# CONTROL.net
KiCad netlist of a schematic drawn in Altium Designer
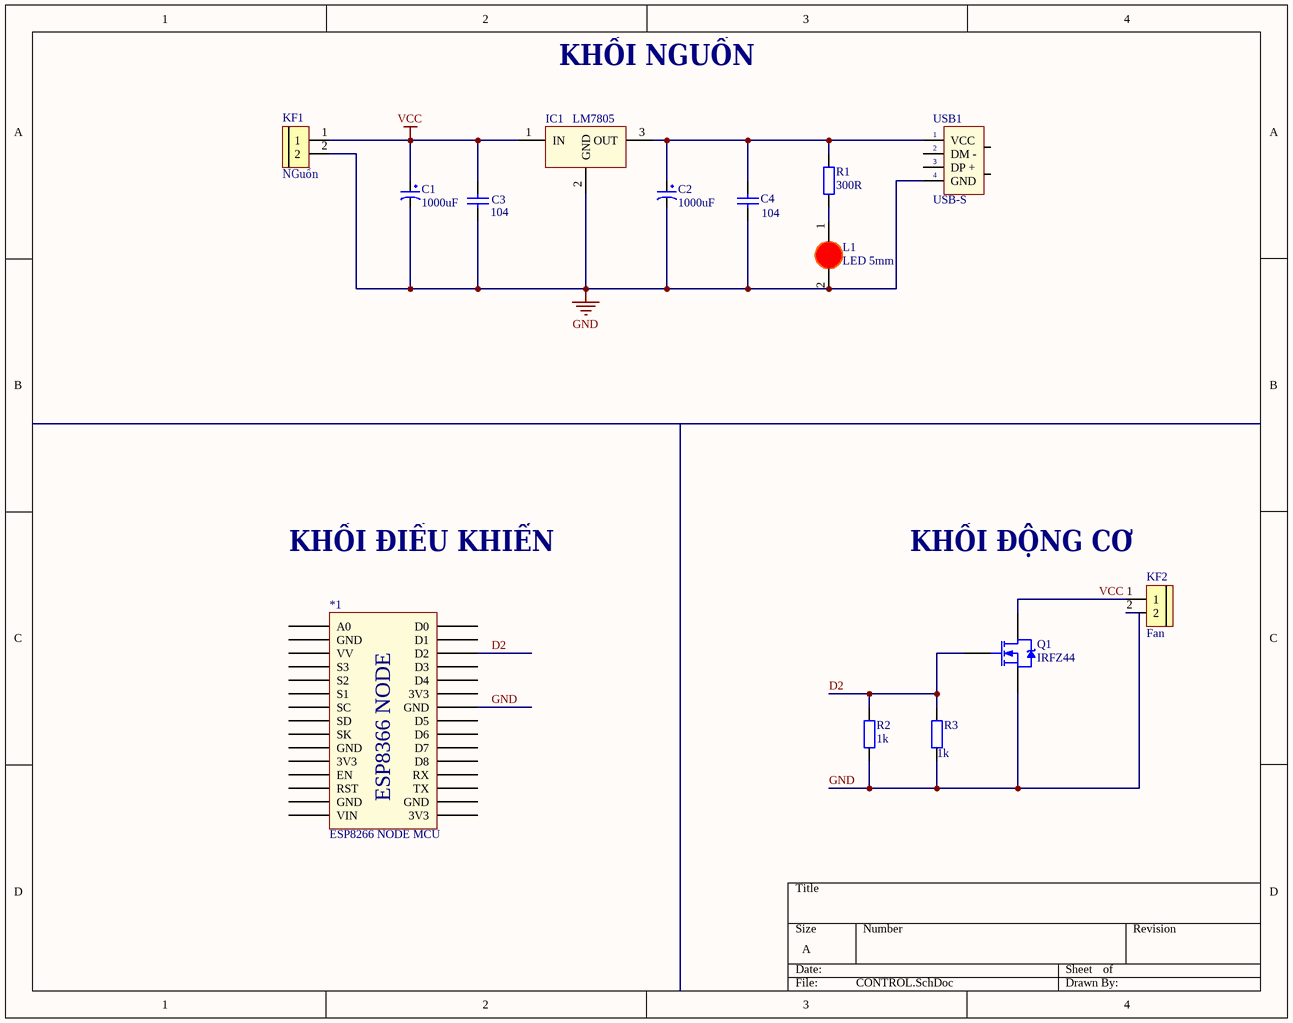
[diagram p0: CONTROL.SchDoc]

(export (version "E")
  (design (tool "Eeschema 10.0.6"))
  (components
    (comp (ref "*1")
      (value "ESP8266 NODE MCU")
      (footprint "ESP8266 NODE MCU")
      (libsource (lib "Module") (part "ESP8266 NODE MCU"))
    )
    (comp (ref "C1")
      (value "1000uF")
      (footprint "tu hoa 10mm")
      (description "Cắm")
      (libsource (lib "Capacitor") (part "Tu Hoa 1000uF 10V 10x12"))
    )
    (comp (ref "C2")
      (value "1000uF")
      (footprint "tu hoa 10mm")
      (description "Cắm")
      (libsource (lib "Capacitor") (part "Tu Hoa 1000uF 10V 10x12"))
    )
    (comp (ref "C3")
      (value "104")
      (footprint "tu gom")
      (description "Cắm")
      (libsource (lib "Capacitor") (part "Tu gom 104 50V"))
    )
    (comp (ref "C4")
      (value "104")
      (footprint "tu gom")
      (description "Cắm")
      (libsource (lib "Capacitor") (part "Tu gom 104 50V"))
    )
    (comp (ref "IC1")
      (value "LM7805")
      (footprint "QTO-220")
      (description "On ap +, from + 5 to + 24VDC")
      (libsource (lib "Cty1") (part "LM78xx"))
    )
    (comp (ref "KF1")
      (value "NGuồn")
      (footprint "Con 2 KF301 5.08")
      (description "Cắm")
      (libsource (lib "") (part "CON 2 KF301_1"))
    )
    (comp (ref "KF2")
      (value "Fan")
      (footprint "Con 2 KF301 5.08")
      (description "Cắm")
      (libsource (lib "Connector") (part "CON 2 KF301"))
    )
    (comp (ref "L1")
      (value "LED 5mm")
      (footprint "LED-5MM-RED")
      (description "Cắm")
      (libsource (lib "Led") (part "LED 5mm Do"))
    )
    (comp (ref "Q1")
      (value "IRFZ44")
      (footprint "TO220")
      (description "TO-220")
      (libsource (lib "TranFet") (part "FET IRFZ44 DIP"))
    )
    (comp (ref "R1")
      (value "300R")
      (footprint "tro vach 1/4w")
      (description "Cắm")
      (libsource (lib "Resistor") (part "Tro Vach 1/4W 5% 300R"))
    )
    (comp (ref "R2")
      (value "1k")
      (footprint "tro vach 1/2w")
      (description "Cắm")
      (libsource (lib "Resistor") (part "Tro Vach 1/2W 5% 1k"))
    )
    (comp (ref "R3")
      (value "1k")
      (footprint "tro vach 1/2w")
      (description "Cắm")
      (libsource (lib "Resistor") (part "Tro Vach 1/2W 5% 1k"))
    )
    (comp (ref "USB1")
      (value "USB-S")
      (footprint "USB-S1")
      (description "USB connector")
      (libsource (lib "Library AL") (part "USB_S"))
    )
  )
  (nets
    (net (code "1") (name "/D2") (class "Default")
      (node (ref "*1") (pin "28") (pinfunction "D2_28") (pintype "passive"))
      (node (ref "Q1") (pin "1") (pinfunction "G_1") (pintype "passive"))
      (node (ref "R2") (pin "2") (pinfunction "2_2") (pintype "passive"))
      (node (ref "R3") (pin "2") (pinfunction "2_2") (pintype "passive"))
    )
    (net (code "2") (name "GND") (class "Default")
      (node (ref "*1") (pin "24") (pinfunction "GND_24") (pintype "passive"))
      (node (ref "C1") (pin "2") (pinfunction "2_2") (pintype "passive"))
      (node (ref "C2") (pin "2") (pinfunction "2_2") (pintype "passive"))
      (node (ref "C3") (pin "1") (pinfunction "1_1") (pintype "passive"))
      (node (ref "C4") (pin "1") (pinfunction "1_1") (pintype "passive"))
      (node (ref "IC1") (pin "2") (pinfunction "GND_2") (pintype "passive"))
      (node (ref "KF1") (pin "2") (pinfunction "2_2") (pintype "passive"))
      (node (ref "KF2") (pin "2") (pinfunction "2_2") (pintype "passive"))
      (node (ref "L1") (pin "2") (pinfunction "K_2") (pintype "passive"))
      (node (ref "Q1") (pin "3") (pinfunction "S_3") (pintype "passive"))
      (node (ref "R2") (pin "1") (pinfunction "1_1") (pintype "passive"))
      (node (ref "R3") (pin "1") (pinfunction "1_1") (pintype "passive"))
      (node (ref "USB1") (pin "4") (pinfunction "GND_4") (pintype "passive"))
    )
    (net (code "3") (name "Net-(IC1-OUT)") (class "Default")
      (node (ref "C2") (pin "1") (pinfunction "1_1") (pintype "passive"))
      (node (ref "C4") (pin "2") (pinfunction "2_2") (pintype "passive"))
      (node (ref "IC1") (pin "3") (pinfunction "OUT_3") (pintype "passive"))
      (node (ref "R1") (pin "2") (pinfunction "2_2") (pintype "passive"))
      (node (ref "USB1") (pin "1") (pinfunction "VCC_1") (pintype "passive"))
    )
    (net (code "4") (name "Net-(L1-A)") (class "Default")
      (node (ref "L1") (pin "1") (pinfunction "A_1") (pintype "passive"))
      (node (ref "R1") (pin "1") (pinfunction "1_1") (pintype "passive"))
    )
    (net (code "5") (name "VCC") (class "Default")
      (node (ref "C1") (pin "1") (pinfunction "1_1") (pintype "passive"))
      (node (ref "C3") (pin "2") (pinfunction "2_2") (pintype "passive"))
      (node (ref "IC1") (pin "1") (pinfunction "IN_1") (pintype "passive"))
      (node (ref "KF1") (pin "1") (pinfunction "1_1") (pintype "passive"))
      (node (ref "KF2") (pin "1") (pinfunction "1_1") (pintype "passive"))
      (node (ref "Q1") (pin "2") (pinfunction "D_2") (pintype "passive"))
    )
    (net (code "6") (name "unconnected-(*1-3V3-Pad11)") (class "Default")
      (node (ref "*1") (pin "11") (pinfunction "3V3_11") (pintype "passive"))
    )
    (net (code "7") (name "unconnected-(*1-3V3-Pad16)") (class "Default")
      (node (ref "*1") (pin "16") (pinfunction "3V3_16") (pintype "passive"))
    )
    (net (code "8") (name "unconnected-(*1-3V3-Pad25)") (class "Default")
      (node (ref "*1") (pin "25") (pinfunction "3V3_25") (pintype "passive"))
    )
    (net (code "9") (name "unconnected-(*1-A0-Pad1)") (class "Default")
      (node (ref "*1") (pin "1") (pinfunction "A0_1") (pintype "passive"))
    )
    (net (code "10") (name "unconnected-(*1-D0-Pad30)") (class "Default")
      (node (ref "*1") (pin "30") (pinfunction "D0_30") (pintype "passive"))
    )
    (net (code "11") (name "unconnected-(*1-D1-Pad29)") (class "Default")
      (node (ref "*1") (pin "29") (pinfunction "D1_29") (pintype "passive"))
    )
    (net (code "12") (name "unconnected-(*1-D3-Pad27)") (class "Default")
      (node (ref "*1") (pin "27") (pinfunction "D3_27") (pintype "passive"))
    )
    (net (code "13") (name "unconnected-(*1-D4-Pad26)") (class "Default")
      (node (ref "*1") (pin "26") (pinfunction "D4_26") (pintype "passive"))
    )
    (net (code "14") (name "unconnected-(*1-D5-Pad23)") (class "Default")
      (node (ref "*1") (pin "23") (pinfunction "D5_23") (pintype "passive"))
    )
    (net (code "15") (name "unconnected-(*1-D6-Pad22)") (class "Default")
      (node (ref "*1") (pin "22") (pinfunction "D6_22") (pintype "passive"))
    )
    (net (code "16") (name "unconnected-(*1-D7-Pad21)") (class "Default")
      (node (ref "*1") (pin "21") (pinfunction "D7_21") (pintype "passive"))
    )
    (net (code "17") (name "unconnected-(*1-D8-Pad20)") (class "Default")
      (node (ref "*1") (pin "20") (pinfunction "D8_20") (pintype "passive"))
    )
    (net (code "18") (name "unconnected-(*1-EN-Pad12)") (class "Default")
      (node (ref "*1") (pin "12") (pinfunction "EN_12") (pintype "passive"))
    )
    (net (code "19") (name "unconnected-(*1-GND-Pad2)") (class "Default")
      (node (ref "*1") (pin "2") (pinfunction "GND_2") (pintype "passive"))
    )
    (net (code "20") (name "unconnected-(*1-GND-Pad10)") (class "Default")
      (node (ref "*1") (pin "10") (pinfunction "GND_10") (pintype "passive"))
    )
    (net (code "21") (name "unconnected-(*1-GND-Pad14)") (class "Default")
      (node (ref "*1") (pin "14") (pinfunction "GND_14") (pintype "passive"))
    )
    (net (code "22") (name "unconnected-(*1-GND-Pad17)") (class "Default")
      (node (ref "*1") (pin "17") (pinfunction "GND_17") (pintype "passive"))
    )
    (net (code "23") (name "unconnected-(*1-RST-Pad13)") (class "Default")
      (node (ref "*1") (pin "13") (pinfunction "RST_13") (pintype "passive"))
    )
    (net (code "24") (name "unconnected-(*1-RX-Pad19)") (class "Default")
      (node (ref "*1") (pin "19") (pinfunction "RX_19") (pintype "passive"))
    )
    (net (code "25") (name "unconnected-(*1-S1-Pad6)") (class "Default")
      (node (ref "*1") (pin "6") (pinfunction "S1_6") (pintype "passive"))
    )
    (net (code "26") (name "unconnected-(*1-S2-Pad5)") (class "Default")
      (node (ref "*1") (pin "5") (pinfunction "S2_5") (pintype "passive"))
    )
    (net (code "27") (name "unconnected-(*1-S3-Pad4)") (class "Default")
      (node (ref "*1") (pin "4") (pinfunction "S3_4") (pintype "passive"))
    )
    (net (code "28") (name "unconnected-(*1-SC-Pad7)") (class "Default")
      (node (ref "*1") (pin "7") (pinfunction "SC_7") (pintype "passive"))
    )
    (net (code "29") (name "unconnected-(*1-SD-Pad8)") (class "Default")
      (node (ref "*1") (pin "8") (pinfunction "SD_8") (pintype "passive"))
    )
    (net (code "30") (name "unconnected-(*1-SK-Pad9)") (class "Default")
      (node (ref "*1") (pin "9") (pinfunction "SK_9") (pintype "passive"))
    )
    (net (code "31") (name "unconnected-(*1-TX-Pad18)") (class "Default")
      (node (ref "*1") (pin "18") (pinfunction "TX_18") (pintype "passive"))
    )
    (net (code "32") (name "unconnected-(*1-VIN-Pad15)") (class "Default")
      (node (ref "*1") (pin "15") (pinfunction "VIN_15") (pintype "passive"))
    )
    (net (code "33") (name "unconnected-(*1-VV-Pad3)") (class "Default")
      (node (ref "*1") (pin "3") (pinfunction "VV_3") (pintype "passive"))
    )
    (net (code "34") (name "unconnected-(USB1-DM_--Pad2)") (class "Default")
      (node (ref "USB1") (pin "2") (pinfunction "DM_-_2") (pintype "passive"))
    )
    (net (code "35") (name "unconnected-(USB1-DP_+-Pad3)") (class "Default")
      (node (ref "USB1") (pin "3") (pinfunction "DP_+_3") (pintype "passive"))
    )
    (net (code "36") (name "unconnected-(USB1-Pad5)") (class "Default")
      (node (ref "USB1") (pin "5") (pinfunction "5_5") (pintype "passive"))
    )
    (net (code "37") (name "unconnected-(USB1-Pad6)") (class "Default")
      (node (ref "USB1") (pin "6") (pinfunction "6_6") (pintype "passive"))
    )
  )
)
